# burglar_alarm.net
KiCad netlist of a schematic drawn in EAGLE
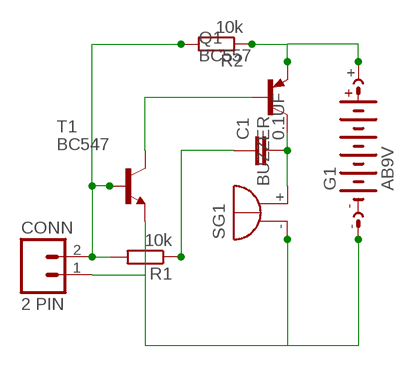
[diagram p0: schematic, sheet 1]

(export (version "E")
  (design (tool "Eeschema 10.0.6"))
  (components
    (comp (ref "C1")
      (value "0.1UF")
      (footprint "eagle-import:C2.5-2")
      (libsource (lib "eagle-import") (part "C2.5/2"))
    )
    (comp (ref "CONN")
      (value "2 PIN")
      (footprint "eagle-import:02P")
      (libsource (lib "eagle-import") (part "M02"))
    )
    (comp (ref "G1")
      (value "AB9V")
      (footprint "eagle-import:AB9V")
      (libsource (lib "eagle-import") (part "AB9V"))
    )
    (comp (ref "Q1")
      (value "BC557")
      (footprint "eagle-import:TO92")
      (libsource (lib "eagle-import") (part "BC557"))
    )
    (comp (ref "R1")
      (value "10k")
      (footprint "eagle-import:0204_5")
      (libsource (lib "eagle-import") (part "R-EU_0204/5"))
    )
    (comp (ref "R2")
      (value "10k")
      (footprint "eagle-import:0204_5")
      (libsource (lib "eagle-import") (part "R-EU_0204/5"))
    )
    (comp (ref "SG1")
      (value "BUZZER")
      (footprint "eagle-import:F_QMB")
      (libsource (lib "eagle-import") (part "F/QMB"))
    )
    (comp (ref "T1")
      (value "BC547")
      (footprint "eagle-import:TO92")
      (libsource (lib "eagle-import") (part "BC547"))
    )
  )
  (nets
    (net (code "1") (name "Net-(C1-Pad1)") (class "Default")
      (node (ref "C1") (pin "1") (pinfunction "1_1") (pintype "passive"))
      (node (ref "R1") (pin "1") (pinfunction "1_1") (pintype "passive"))
    )
    (net (code "2") (name "Net-(Q1-B)") (class "Default")
      (node (ref "Q1") (pin "2") (pinfunction "B_2") (pintype "passive"))
      (node (ref "T1") (pin "3") (pinfunction "C_3") (pintype "passive"))
    )
    (net (code "3") (name "Net-(Q1-C)") (class "Default")
      (node (ref "C1") (pin "2") (pinfunction "2_2") (pintype "passive"))
      (node (ref "Q1") (pin "3") (pinfunction "C_3") (pintype "passive"))
      (node (ref "SG1") (pin "+") (pinfunction "-_+") (pintype "passive"))
    )
    (net (code "4") (name "Net-(Q1-E)") (class "Default")
      (node (ref "G1") (pin "+") (pinfunction "+_+") (pintype "passive"))
      (node (ref "Q1") (pin "1") (pinfunction "E_1") (pintype "passive"))
      (node (ref "R2") (pin "1") (pinfunction "1_1") (pintype "passive"))
    )
    (net (code "5") (name "Net-(SG1-+)") (class "Default")
      (node (ref "CONN") (pin "1") (pinfunction "1_1") (pintype "passive"))
      (node (ref "G1") (pin "-") (pinfunction "-_-") (pintype "passive"))
      (node (ref "SG1") (pin "-") (pinfunction "+_-") (pintype "passive"))
      (node (ref "T1") (pin "1") (pinfunction "E_1") (pintype "passive"))
    )
    (net (code "6") (name "Net-(T1-B)") (class "Default")
      (node (ref "CONN") (pin "2") (pinfunction "2_2") (pintype "passive"))
      (node (ref "R1") (pin "2") (pinfunction "2_2") (pintype "passive"))
      (node (ref "R2") (pin "2") (pinfunction "2_2") (pintype "passive"))
      (node (ref "T1") (pin "2") (pinfunction "B_2") (pintype "passive"))
    )
  )
)
